# passive-optothing.net
KiCad netlist of a schematic drawn in EAGLE
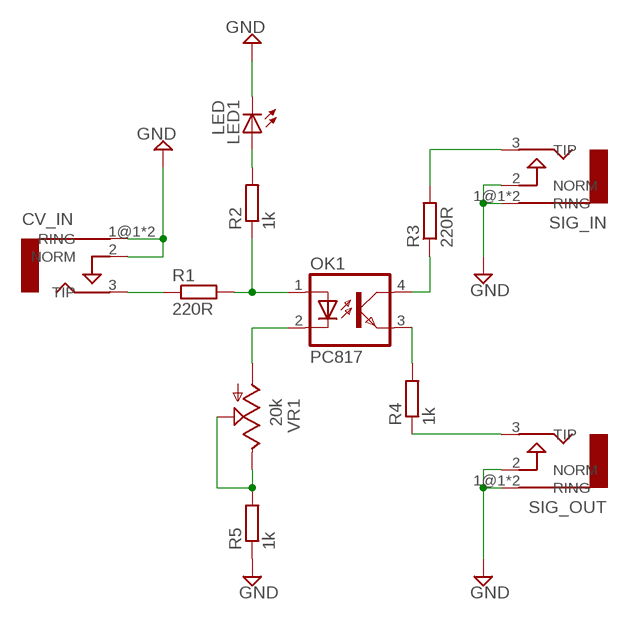
[diagram p0: schematic, sheet 1]

(export (version "E")
  (design (tool "Eeschema 10.0.6"))
  (components
    (comp (ref "CV_IN")
      (value "AUDIO-JACKERTHENVAR")
      (footprint "eagle-import:ERTHENVAR-JACK")
      (libsource (lib "eagle-import") (part "AUDIO-JACKERTHENVAR"))
    )
    (comp (ref "LED1")
      (value "LED")
      (footprint "eagle-import:LED3MM")
      (libsource (lib "eagle-import") (part "LED3MM"))
    )
    (comp (ref "OK1")
      (value "PC817")
      (footprint "eagle-import:DIL04")
      (fields (field (name "MPN") "PC817X4J000F"))
      (libsource (lib "eagle-import") (part "PC817"))
    )
    (comp (ref "R1")
      (value "220R")
      (footprint "eagle-import:R0805")
      (libsource (lib "eagle-import") (part "R-EU_R0805"))
    )
    (comp (ref "R2")
      (value "1k")
      (footprint "eagle-import:R0805")
      (libsource (lib "eagle-import") (part "R-EU_R0805"))
    )
    (comp (ref "R3")
      (value "220R")
      (footprint "eagle-import:R0805")
      (libsource (lib "eagle-import") (part "R-EU_R0805"))
    )
    (comp (ref "R4")
      (value "1k")
      (footprint "eagle-import:R0805")
      (libsource (lib "eagle-import") (part "R-EU_R0805"))
    )
    (comp (ref "R5")
      (value "1k")
      (footprint "eagle-import:R0805")
      (libsource (lib "eagle-import") (part "R-EU_R0805"))
    )
    (comp (ref "SIG_IN")
      (value "AUDIO-JACKERTHENVAR")
      (footprint "eagle-import:ERTHENVAR-JACK")
      (libsource (lib "eagle-import") (part "AUDIO-JACKERTHENVAR"))
    )
    (comp (ref "SIG_OUT")
      (value "AUDIO-JACKERTHENVAR")
      (footprint "eagle-import:ERTHENVAR-JACK")
      (libsource (lib "eagle-import") (part "AUDIO-JACKERTHENVAR"))
    )
    (comp (ref "VR1")
      (value "20k")
      (footprint "eagle-import:9MM_SNAP-IN_POT")
      (libsource (lib "eagle-import") (part "9MM_SNAP-IN_POT_"))
    )
  )
  (nets
    (net (code "1") (name "GND") (class "Default")
      (node (ref "CV_IN") (pin "1@1") (pinfunction "RING_1@1") (pintype "bidirectional"))
      (node (ref "CV_IN") (pin "1@2") (pinfunction "RING_1@2") (pintype "bidirectional"))
      (node (ref "CV_IN") (pin "2") (pinfunction "NORM_2") (pintype "bidirectional"))
      (node (ref "LED1") (pin "K") (pinfunction "C_K") (pintype "passive"))
      (node (ref "R5") (pin "1") (pinfunction "1_1") (pintype "passive"))
      (node (ref "SIG_IN") (pin "1@1") (pinfunction "RING_1@1") (pintype "bidirectional"))
      (node (ref "SIG_IN") (pin "1@2") (pinfunction "RING_1@2") (pintype "bidirectional"))
      (node (ref "SIG_IN") (pin "2") (pinfunction "NORM_2") (pintype "bidirectional"))
      (node (ref "SIG_OUT") (pin "1@1") (pinfunction "RING_1@1") (pintype "bidirectional"))
      (node (ref "SIG_OUT") (pin "1@2") (pinfunction "RING_1@2") (pintype "bidirectional"))
      (node (ref "SIG_OUT") (pin "2") (pinfunction "NORM_2") (pintype "bidirectional"))
    )
    (net (code "2") (name "Net-(CV_IN-TIP)") (class "Default")
      (node (ref "CV_IN") (pin "3") (pinfunction "TIP_3") (pintype "bidirectional"))
      (node (ref "R1") (pin "1") (pinfunction "1_1") (pintype "passive"))
    )
    (net (code "3") (name "Net-(LED1-PadA)") (class "Default")
      (node (ref "LED1") (pin "A") (pinfunction "A_A") (pintype "passive"))
      (node (ref "R2") (pin "2") (pinfunction "2_2") (pintype "passive"))
    )
    (net (code "4") (name "Net-(OK1-A)") (class "Default")
      (node (ref "OK1") (pin "1") (pinfunction "A_1") (pintype "passive"))
      (node (ref "R1") (pin "2") (pinfunction "2_2") (pintype "passive"))
      (node (ref "R2") (pin "1") (pinfunction "1_1") (pintype "passive"))
    )
    (net (code "5") (name "Net-(OK1-C)") (class "Default")
      (node (ref "OK1") (pin "2") (pinfunction "C_2") (pintype "passive"))
      (node (ref "VR1") (pin "1") (pinfunction "A_1") (pintype "passive"))
    )
    (net (code "6") (name "Net-(OK1-COL)") (class "Default")
      (node (ref "OK1") (pin "4") (pinfunction "COL_4") (pintype "passive"))
      (node (ref "R3") (pin "1") (pinfunction "1_1") (pintype "passive"))
    )
    (net (code "7") (name "Net-(OK1-EMIT)") (class "Default")
      (node (ref "OK1") (pin "3") (pinfunction "EMIT_3") (pintype "passive"))
      (node (ref "R4") (pin "2") (pinfunction "2_2") (pintype "passive"))
    )
    (net (code "8") (name "Net-(SIG_IN-TIP)") (class "Default")
      (node (ref "R3") (pin "2") (pinfunction "2_2") (pintype "passive"))
      (node (ref "SIG_IN") (pin "3") (pinfunction "TIP_3") (pintype "bidirectional"))
    )
    (net (code "9") (name "Net-(SIG_OUT-TIP)") (class "Default")
      (node (ref "R4") (pin "1") (pinfunction "1_1") (pintype "passive"))
      (node (ref "SIG_OUT") (pin "3") (pinfunction "TIP_3") (pintype "bidirectional"))
    )
    (net (code "10") (name "Net-(VR1-E)") (class "Default")
      (node (ref "R5") (pin "2") (pinfunction "2_2") (pintype "passive"))
      (node (ref "VR1") (pin "2") (pinfunction "S_2") (pintype "passive"))
      (node (ref "VR1") (pin "3") (pinfunction "E_3") (pintype "passive"))
    )
  )
)
